# 15321_2.net
KiCad netlist of a schematic drawn in EAGLE
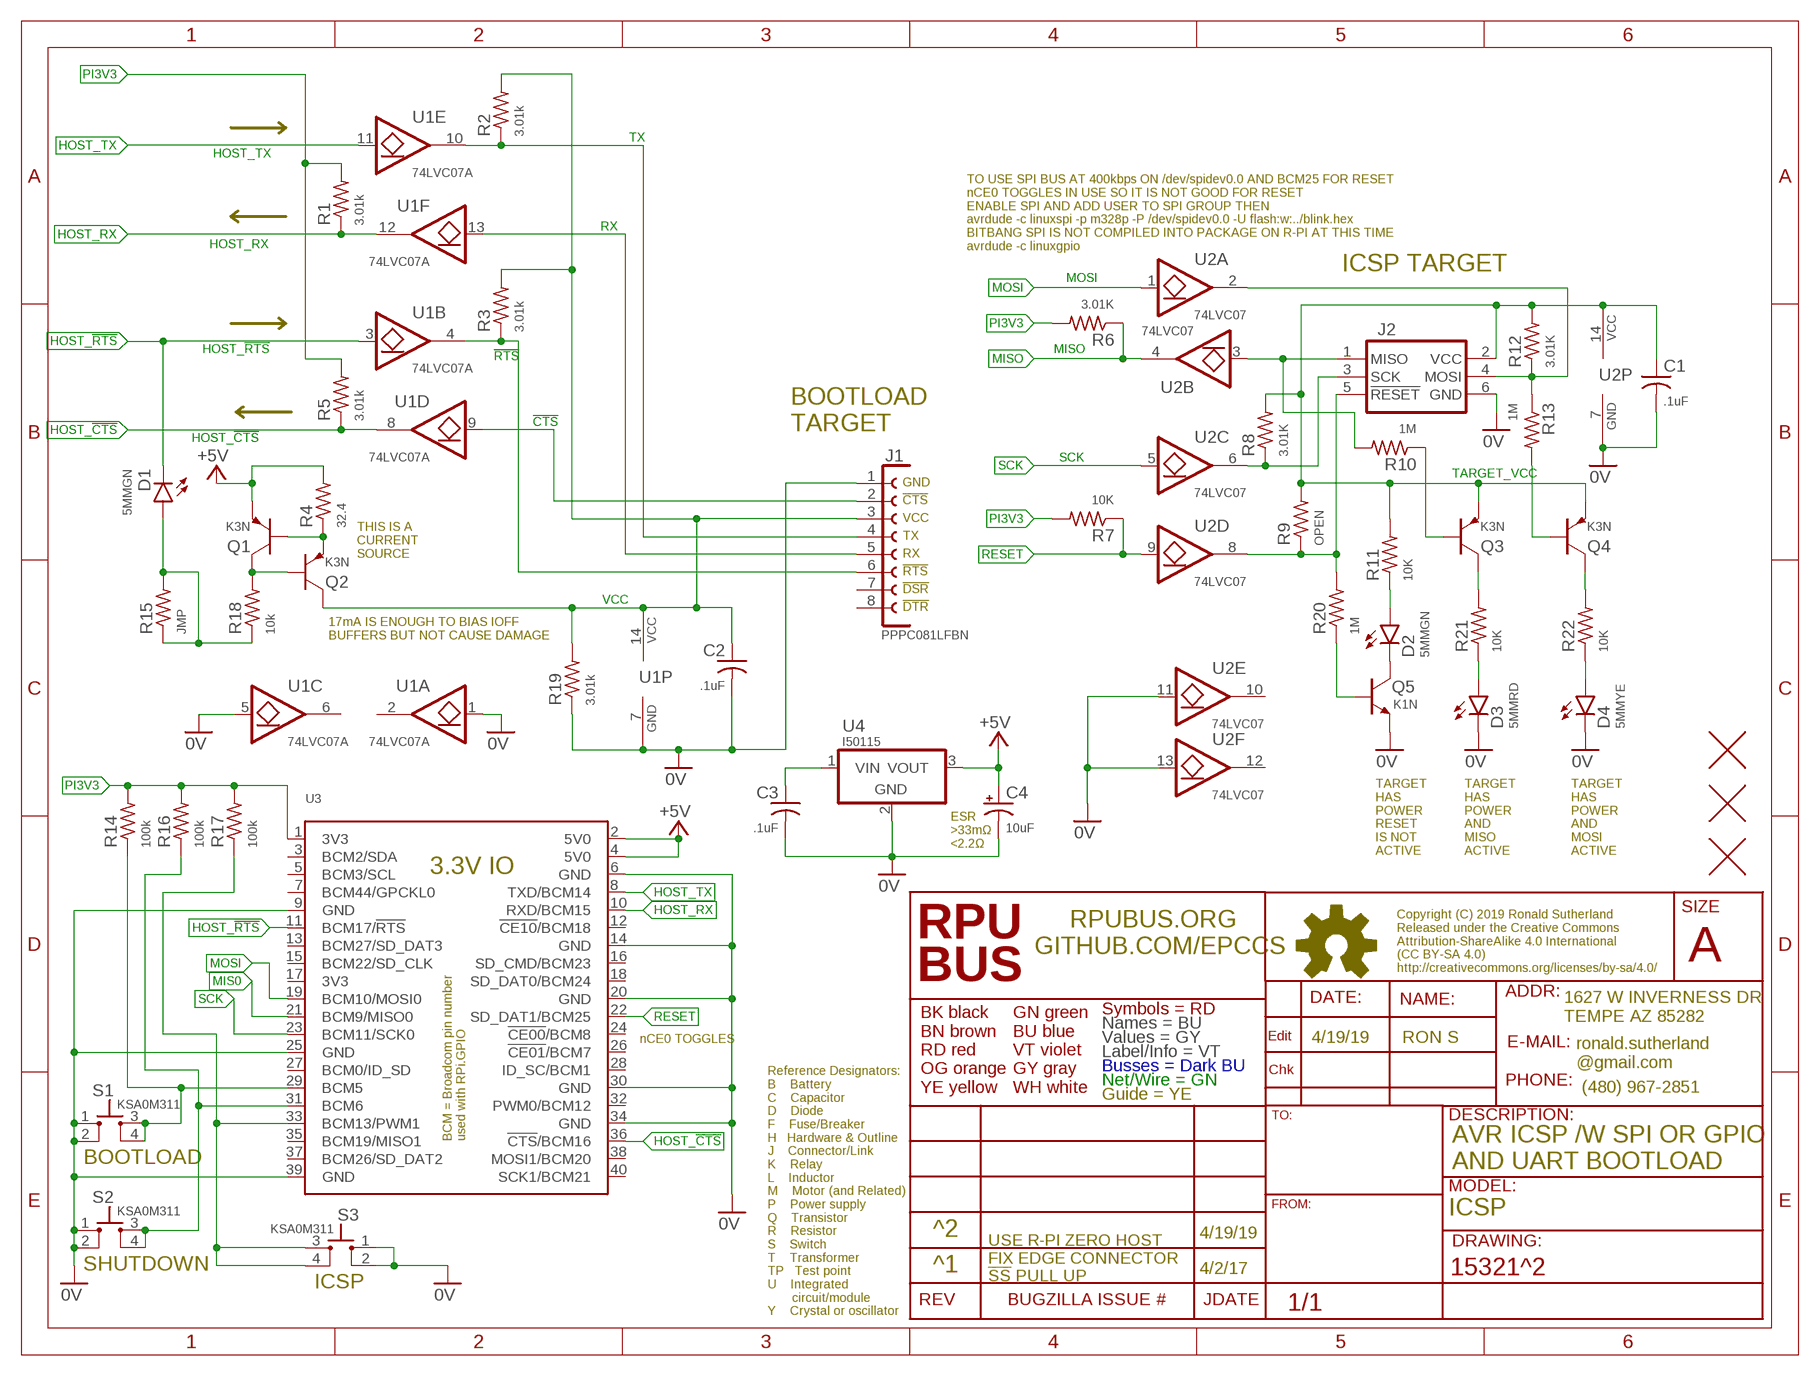
[diagram p0: schematic, sheet 1]

(export (version "E")
  (design (tool "Eeschema 10.0.6"))
  (components
    (comp (ref "C1")
      (value ".1uF")
      (footprint "eagle-import:C0603(1608)")
      (libsource (lib "eagle-import") (part "CC0603A"))
    )
    (comp (ref "C2")
      (value ".1uF")
      (footprint "eagle-import:C0603(1608)")
      (libsource (lib "eagle-import") (part "CC0603A"))
    )
    (comp (ref "C3")
      (value ".1uF")
      (footprint "eagle-import:C0603(1608)")
      (libsource (lib "eagle-import") (part "CC0603A"))
    )
    (comp (ref "C4")
      (value "10uF")
      (footprint "eagle-import:3216")
      (libsource (lib "eagle-import") (part "CT1206"))
    )
    (comp (ref "D1")
      (value "5MMGN")
      (footprint "eagle-import:LED5MM")
      (libsource (lib "eagle-import") (part "LED5MM"))
    )
    (comp (ref "D2")
      (value "5MMGN")
      (footprint "eagle-import:LED5MM")
      (libsource (lib "eagle-import") (part "LED5MM"))
    )
    (comp (ref "D3")
      (value "5MMRD")
      (footprint "eagle-import:LED5MM")
      (libsource (lib "eagle-import") (part "LED5MM"))
    )
    (comp (ref "D4")
      (value "5MMYE")
      (footprint "eagle-import:LED5MM")
      (libsource (lib "eagle-import") (part "LED5MM"))
    )
    (comp (ref "J1")
      (value "PPPC081LFBN")
      (footprint "eagle-import:F1X8")
      (libsource (lib "eagle-import") (part "F1X8"))
    )
    (comp (ref "J2")
      (value "ISP-SPIEDG")
      (footprint "eagle-import:ISP-EDG")
      (libsource (lib "eagle-import") (part "ISP-SPIEDG"))
    )
    (comp (ref "Q1")
      (value "K3N")
      (footprint "eagle-import:SOT23")
      (libsource (lib "eagle-import") (part "PNPSOT23"))
    )
    (comp (ref "Q2")
      (value "K3N")
      (footprint "eagle-import:SOT23")
      (libsource (lib "eagle-import") (part "PNPSOT23"))
    )
    (comp (ref "Q3")
      (value "K3N")
      (footprint "eagle-import:SOT23")
      (libsource (lib "eagle-import") (part "PNPSOT23"))
    )
    (comp (ref "Q4")
      (value "K3N")
      (footprint "eagle-import:SOT23")
      (libsource (lib "eagle-import") (part "PNPSOT23"))
    )
    (comp (ref "Q5")
      (value "K1N")
      (footprint "eagle-import:SOT23")
      (libsource (lib "eagle-import") (part "NPNSOT23"))
    )
    (comp (ref "R1")
      (value "3.01k")
      (footprint "eagle-import:C0805(2012)")
      (libsource (lib "eagle-import") (part "R0805"))
    )
    (comp (ref "R2")
      (value "3.01k")
      (footprint "eagle-import:C0805(2012)")
      (libsource (lib "eagle-import") (part "R0805"))
    )
    (comp (ref "R3")
      (value "3.01k")
      (footprint "eagle-import:C0805(2012)")
      (libsource (lib "eagle-import") (part "R0805"))
    )
    (comp (ref "R4")
      (value "32.4")
      (footprint "eagle-import:C0805(2012)")
      (libsource (lib "eagle-import") (part "R0805"))
    )
    (comp (ref "R5")
      (value "3.01k")
      (footprint "eagle-import:C0805(2012)")
      (libsource (lib "eagle-import") (part "R0805"))
    )
    (comp (ref "R6")
      (value "3.01K")
      (footprint "eagle-import:C0805(2012)")
      (libsource (lib "eagle-import") (part "R0805"))
    )
    (comp (ref "R7")
      (value "10K")
      (footprint "eagle-import:C0805(2012)")
      (libsource (lib "eagle-import") (part "R0805"))
    )
    (comp (ref "R8")
      (value "3.01K")
      (footprint "eagle-import:C0805(2012)")
      (libsource (lib "eagle-import") (part "R0805"))
    )
    (comp (ref "R9")
      (value "OPEN")
      (footprint "eagle-import:C0805(2012)")
      (libsource (lib "eagle-import") (part "R0805"))
    )
    (comp (ref "R10")
      (value "1M")
      (footprint "eagle-import:C0805(2012)")
      (libsource (lib "eagle-import") (part "R0805"))
    )
    (comp (ref "R11")
      (value "10K")
      (footprint "eagle-import:C0805(2012)")
      (libsource (lib "eagle-import") (part "R0805"))
    )
    (comp (ref "R12")
      (value "3.01K")
      (footprint "eagle-import:C0805(2012)")
      (libsource (lib "eagle-import") (part "R0805"))
    )
    (comp (ref "R13")
      (value "1M")
      (footprint "eagle-import:C0805(2012)")
      (libsource (lib "eagle-import") (part "R0805"))
    )
    (comp (ref "R14")
      (value "100k")
      (footprint "eagle-import:C0805(2012)")
      (libsource (lib "eagle-import") (part "R0805"))
    )
    (comp (ref "R15")
      (value "JMP")
      (footprint "eagle-import:C0805(2012)")
      (libsource (lib "eagle-import") (part "R0805"))
    )
    (comp (ref "R16")
      (value "100k")
      (footprint "eagle-import:C0805(2012)")
      (libsource (lib "eagle-import") (part "R0805"))
    )
    (comp (ref "R17")
      (value "100k")
      (footprint "eagle-import:C0805(2012)")
      (libsource (lib "eagle-import") (part "R0805"))
    )
    (comp (ref "R18")
      (value "10k")
      (footprint "eagle-import:C0805(2012)")
      (libsource (lib "eagle-import") (part "R0805"))
    )
    (comp (ref "R19")
      (value "3.01k")
      (footprint "eagle-import:C0805(2012)")
      (libsource (lib "eagle-import") (part "R0805"))
    )
    (comp (ref "R20")
      (value "1M")
      (footprint "eagle-import:C0805(2012)")
      (libsource (lib "eagle-import") (part "R0805"))
    )
    (comp (ref "R21")
      (value "10K")
      (footprint "eagle-import:C0805(2012)")
      (libsource (lib "eagle-import") (part "R0805"))
    )
    (comp (ref "R22")
      (value "10K")
      (footprint "eagle-import:C0805(2012)")
      (libsource (lib "eagle-import") (part "R0805"))
    )
    (comp (ref "S1")
      (value "KSA0M311")
      (footprint "eagle-import:0M311")
      (libsource (lib "eagle-import") (part "KSA0M311"))
    )
    (comp (ref "S2")
      (value "KSA0M311")
      (footprint "eagle-import:0M311")
      (libsource (lib "eagle-import") (part "KSA0M311"))
    )
    (comp (ref "S3")
      (value "KSA0M311")
      (footprint "eagle-import:0M311")
      (libsource (lib "eagle-import") (part "KSA0M311"))
    )
    (comp (ref "U$2")
      (value "FIDUCIAL1.27")
      (footprint "eagle-import:FIDUCIAL-1.27")
      (libsource (lib "eagle-import") (part "FIDUCIAL1.27"))
    )
    (comp (ref "U$3")
      (value "FIDUCIAL1.27")
      (footprint "eagle-import:FIDUCIAL-1.27")
      (libsource (lib "eagle-import") (part "FIDUCIAL1.27"))
    )
    (comp (ref "U$4")
      (value "FIDUCIAL1.27")
      (footprint "eagle-import:FIDUCIAL-1.27")
      (libsource (lib "eagle-import") (part "FIDUCIAL1.27"))
    )
    (comp (ref "U1")
      (value "74LVC07A")
      (footprint "eagle-import:14SOIC")
      (libsource (lib "eagle-import") (part "7407D"))
    )
    (comp (ref "U2")
      (value "74LVC07")
      (footprint "eagle-import:14SOIC")
      (libsource (lib "eagle-import") (part "7407D"))
    )
    (comp (ref "U3")
      (value "RPI-ZERO")
      (footprint "eagle-import:RASPI_ZERO_H40PIN")
      (libsource (lib "eagle-import") (part "RPI-ZERO"))
    )
    (comp (ref "U4")
      (value "I50115")
      (footprint "eagle-import:OKI-78SR-H")
      (libsource (lib "eagle-import") (part "OKI-78SR-H"))
    )
  )
  (nets
    (net (code "1") (name "+5V") (class "Default")
      (node (ref "C4") (pin "+") (pinfunction "+_+") (pintype "passive"))
      (node (ref "Q1") (pin "E") (pinfunction "E_E") (pintype "passive"))
      (node (ref "R4") (pin "2") (pinfunction "2_2") (pintype "passive"))
      (node (ref "U3") (pin "2") (pinfunction "5V0_2") (pintype "power_in"))
      (node (ref "U3") (pin "4") (pinfunction "5V0_4") (pintype "power_in"))
      (node (ref "U4") (pin "3") (pinfunction "VOUT_3") (pintype "passive"))
    )
    (net (code "2") (name "/3V3") (class "Default")
      (node (ref "U3") (pin "17") (pinfunction "3V3_17") (pintype "power_in"))
    )
    (net (code "3") (name "/HOST_~{CTS}") (class "Default")
      (node (ref "R5") (pin "1") (pinfunction "1_1") (pintype "passive"))
      (node (ref "U1") (pin "8") (pinfunction "O_8") (pintype "open_collector"))
      (node (ref "U3") (pin "36") (pinfunction "~{CTS}/BCM16_36") (pintype "bidirectional"))
    )
    (net (code "4") (name "/HOST_~{RTS}") (class "Default")
      (node (ref "D1") (pin "K") (pinfunction "K_K") (pintype "passive"))
      (node (ref "U1") (pin "3") (pinfunction "I_3") (pintype "input"))
      (node (ref "U3") (pin "11") (pinfunction "BCM17/~{RTS}_11") (pintype "bidirectional"))
    )
    (net (code "5") (name "/RX") (class "Default")
      (node (ref "J1") (pin "5") (pinfunction "5_5") (pintype "passive"))
      (node (ref "U1") (pin "13") (pinfunction "I_13") (pintype "input"))
    )
    (net (code "6") (name "/TARGET_VCC") (class "Default")
      (node (ref "C1") (pin "1") (pinfunction "1_1") (pintype "passive"))
      (node (ref "J2") (pin "2") (pinfunction "VCC_2") (pintype "bidirectional"))
      (node (ref "Q3") (pin "E") (pinfunction "E_E") (pintype "passive"))
      (node (ref "Q4") (pin "E") (pinfunction "E_E") (pintype "passive"))
      (node (ref "R11") (pin "2") (pinfunction "2_2") (pintype "passive"))
      (node (ref "R12") (pin "2") (pinfunction "2_2") (pintype "passive"))
      (node (ref "R8") (pin "2") (pinfunction "2_2") (pintype "passive"))
      (node (ref "R9") (pin "2") (pinfunction "2_2") (pintype "passive"))
      (node (ref "U2") (pin "14") (pinfunction "VCC_14") (pintype "power_in"))
    )
    (net (code "7") (name "/TX") (class "Default")
      (node (ref "J1") (pin "4") (pinfunction "4_4") (pintype "passive"))
      (node (ref "R2") (pin "1") (pinfunction "1_1") (pintype "passive"))
      (node (ref "U1") (pin "10") (pinfunction "O_10") (pintype "open_collector"))
    )
    (net (code "8") (name "/VCC") (class "Default")
      (node (ref "C2") (pin "1") (pinfunction "1_1") (pintype "passive"))
      (node (ref "J1") (pin "3") (pinfunction "3_3") (pintype "passive"))
      (node (ref "Q2") (pin "C") (pinfunction "C_C") (pintype "passive"))
      (node (ref "R19") (pin "2") (pinfunction "2_2") (pintype "passive"))
      (node (ref "R2") (pin "2") (pinfunction "2_2") (pintype "passive"))
      (node (ref "R3") (pin "2") (pinfunction "2_2") (pintype "passive"))
      (node (ref "U1") (pin "14") (pinfunction "VCC_14") (pintype "power_in"))
    )
    (net (code "9") (name "/~{CTS}") (class "Default")
      (node (ref "J1") (pin "2") (pinfunction "2_2") (pintype "passive"))
      (node (ref "U1") (pin "9") (pinfunction "I_9") (pintype "input"))
    )
    (net (code "10") (name "/~{RTS}") (class "Default")
      (node (ref "J1") (pin "6") (pinfunction "6_6") (pintype "passive"))
      (node (ref "R3") (pin "1") (pinfunction "1_1") (pintype "passive"))
      (node (ref "U1") (pin "4") (pinfunction "O_4") (pintype "open_collector"))
    )
    (net (code "11") (name "0V") (class "Default")
      (node (ref "C1") (pin "2") (pinfunction "2_2") (pintype "passive"))
      (node (ref "C2") (pin "2") (pinfunction "2_2") (pintype "passive"))
      (node (ref "C3") (pin "2") (pinfunction "2_2") (pintype "passive"))
      (node (ref "C4") (pin "-") (pinfunction "-_-") (pintype "passive"))
      (node (ref "D3") (pin "K") (pinfunction "K_K") (pintype "passive"))
      (node (ref "D4") (pin "K") (pinfunction "K_K") (pintype "passive"))
      (node (ref "J1") (pin "1") (pinfunction "1_1") (pintype "passive"))
      (node (ref "J2") (pin "6") (pinfunction "GND_6") (pintype "bidirectional"))
      (node (ref "Q5") (pin "E") (pinfunction "E_E") (pintype "passive"))
      (node (ref "R19") (pin "1") (pinfunction "1_1") (pintype "passive"))
      (node (ref "S1") (pin "1") (pinfunction "1_1") (pintype "passive"))
      (node (ref "S1") (pin "2") (pinfunction "2_2") (pintype "passive"))
      (node (ref "S2") (pin "1") (pinfunction "1_1") (pintype "passive"))
      (node (ref "S2") (pin "2") (pinfunction "2_2") (pintype "passive"))
      (node (ref "S3") (pin "1") (pinfunction "1_1") (pintype "passive"))
      (node (ref "S3") (pin "2") (pinfunction "2_2") (pintype "passive"))
      (node (ref "U1") (pin "1") (pinfunction "I_1") (pintype "input"))
      (node (ref "U1") (pin "5") (pinfunction "I_5") (pintype "input"))
      (node (ref "U1") (pin "7") (pinfunction "GND_7") (pintype "power_in"))
      (node (ref "U2") (pin "11") (pinfunction "I_11") (pintype "input"))
      (node (ref "U2") (pin "13") (pinfunction "I_13") (pintype "input"))
      (node (ref "U2") (pin "7") (pinfunction "GND_7") (pintype "power_in"))
      (node (ref "U3") (pin "14") (pinfunction "GND_14") (pintype "power_in"))
      (node (ref "U3") (pin "20") (pinfunction "GND_20") (pintype "power_in"))
      (node (ref "U3") (pin "25") (pinfunction "GND_25") (pintype "power_in"))
      (node (ref "U3") (pin "30") (pinfunction "GND_30") (pintype "power_in"))
      (node (ref "U3") (pin "34") (pinfunction "GND_34") (pintype "power_in"))
      (node (ref "U3") (pin "39") (pinfunction "GND_39") (pintype "power_in"))
      (node (ref "U3") (pin "6") (pinfunction "GND_6") (pintype "power_in"))
      (node (ref "U3") (pin "9") (pinfunction "GND_9") (pintype "power_in"))
      (node (ref "U4") (pin "2") (pinfunction "GND_2") (pintype "passive"))
    )
    (net (code "12") (name "HOST_RX") (class "Default")
      (node (ref "R1") (pin "1") (pinfunction "1_1") (pintype "passive"))
      (node (ref "U1") (pin "12") (pinfunction "O_12") (pintype "open_collector"))
      (node (ref "U3") (pin "10") (pinfunction "RXD/BCM15_10") (pintype "bidirectional"))
    )
    (net (code "13") (name "HOST_TX") (class "Default")
      (node (ref "U1") (pin "11") (pinfunction "I_11") (pintype "input"))
      (node (ref "U3") (pin "8") (pinfunction "TXD/BCM14_8") (pintype "bidirectional"))
    )
    (net (code "14") (name "MIS0") (class "Default")
      (node (ref "U3") (pin "21") (pinfunction "BCM9/MISO0_21") (pintype "bidirectional"))
    )
    (net (code "15") (name "MISO") (class "Default")
      (node (ref "R6") (pin "1") (pinfunction "1_1") (pintype "passive"))
      (node (ref "U2") (pin "4") (pinfunction "O_4") (pintype "open_collector"))
    )
    (net (code "16") (name "MOSI") (class "Default")
      (node (ref "U2") (pin "1") (pinfunction "I_1") (pintype "input"))
      (node (ref "U3") (pin "19") (pinfunction "BCM10/MOSI0_19") (pintype "bidirectional"))
    )
    (net (code "17") (name "Net-(D1-PadA)") (class "Default")
      (node (ref "D1") (pin "A") (pinfunction "A_A") (pintype "passive"))
      (node (ref "R15") (pin "1") (pinfunction "1_1") (pintype "passive"))
      (node (ref "R15") (pin "2") (pinfunction "2_2") (pintype "passive"))
      (node (ref "R18") (pin "1") (pinfunction "1_1") (pintype "passive"))
    )
    (net (code "18") (name "Net-(D2-PadA)") (class "Default")
      (node (ref "D2") (pin "A") (pinfunction "A_A") (pintype "passive"))
      (node (ref "R11") (pin "1") (pinfunction "1_1") (pintype "passive"))
    )
    (net (code "19") (name "Net-(D2-PadK)") (class "Default")
      (node (ref "D2") (pin "K") (pinfunction "K_K") (pintype "passive"))
      (node (ref "Q5") (pin "C") (pinfunction "C_C") (pintype "passive"))
    )
    (net (code "20") (name "Net-(D3-PadA)") (class "Default")
      (node (ref "D3") (pin "A") (pinfunction "A_A") (pintype "passive"))
      (node (ref "R21") (pin "1") (pinfunction "1_1") (pintype "passive"))
    )
    (net (code "21") (name "Net-(D4-PadA)") (class "Default")
      (node (ref "D4") (pin "A") (pinfunction "A_A") (pintype "passive"))
      (node (ref "R22") (pin "1") (pinfunction "1_1") (pintype "passive"))
    )
    (net (code "22") (name "Net-(J2-MISO)") (class "Default")
      (node (ref "J2") (pin "1") (pinfunction "MISO_1") (pintype "bidirectional"))
      (node (ref "R10") (pin "2") (pinfunction "2_2") (pintype "passive"))
      (node (ref "U2") (pin "3") (pinfunction "I_3") (pintype "input"))
    )
    (net (code "23") (name "Net-(J2-MOSI)") (class "Default")
      (node (ref "J2") (pin "4") (pinfunction "MOSI_4") (pintype "bidirectional"))
      (node (ref "R12") (pin "1") (pinfunction "1_1") (pintype "passive"))
      (node (ref "R13") (pin "1") (pinfunction "1_1") (pintype "passive"))
      (node (ref "U2") (pin "2") (pinfunction "O_2") (pintype "open_collector"))
    )
    (net (code "24") (name "Net-(J2-SCK)") (class "Default")
      (node (ref "J2") (pin "3") (pinfunction "SCK_3") (pintype "bidirectional"))
      (node (ref "R8") (pin "1") (pinfunction "1_1") (pintype "passive"))
      (node (ref "U2") (pin "6") (pinfunction "O_6") (pintype "open_collector"))
    )
    (net (code "25") (name "Net-(J2-~{RESET})") (class "Default")
      (node (ref "J2") (pin "5") (pinfunction "~{RESET}_5") (pintype "bidirectional"))
      (node (ref "R20") (pin "2") (pinfunction "2_2") (pintype "passive"))
      (node (ref "R9") (pin "1") (pinfunction "1_1") (pintype "passive"))
      (node (ref "U2") (pin "8") (pinfunction "O_8") (pintype "open_collector"))
    )
    (net (code "26") (name "Net-(Q1-PadB)") (class "Default")
      (node (ref "Q1") (pin "B") (pinfunction "B_B") (pintype "passive"))
      (node (ref "Q2") (pin "E") (pinfunction "E_E") (pintype "passive"))
      (node (ref "R4") (pin "1") (pinfunction "1_1") (pintype "passive"))
    )
    (net (code "27") (name "Net-(Q1-PadC)") (class "Default")
      (node (ref "Q1") (pin "C") (pinfunction "C_C") (pintype "passive"))
      (node (ref "Q2") (pin "B") (pinfunction "B_B") (pintype "passive"))
      (node (ref "R18") (pin "2") (pinfunction "2_2") (pintype "passive"))
    )
    (net (code "28") (name "Net-(Q3-PadB)") (class "Default")
      (node (ref "Q3") (pin "B") (pinfunction "B_B") (pintype "passive"))
      (node (ref "R10") (pin "1") (pinfunction "1_1") (pintype "passive"))
    )
    (net (code "29") (name "Net-(Q3-PadC)") (class "Default")
      (node (ref "Q3") (pin "C") (pinfunction "C_C") (pintype "passive"))
      (node (ref "R21") (pin "2") (pinfunction "2_2") (pintype "passive"))
    )
    (net (code "30") (name "Net-(Q4-PadB)") (class "Default")
      (node (ref "Q4") (pin "B") (pinfunction "B_B") (pintype "passive"))
      (node (ref "R13") (pin "2") (pinfunction "2_2") (pintype "passive"))
    )
    (net (code "31") (name "Net-(Q4-PadC)") (class "Default")
      (node (ref "Q4") (pin "C") (pinfunction "C_C") (pintype "passive"))
      (node (ref "R22") (pin "2") (pinfunction "2_2") (pintype "passive"))
    )
    (net (code "32") (name "Net-(Q5-PadB)") (class "Default")
      (node (ref "Q5") (pin "B") (pinfunction "B_B") (pintype "passive"))
      (node (ref "R20") (pin "1") (pinfunction "1_1") (pintype "passive"))
    )
    (net (code "33") (name "Net-(U3-BCM5)") (class "Default")
      (node (ref "R14") (pin "1") (pinfunction "1_1") (pintype "passive"))
      (node (ref "S1") (pin "3") (pinfunction "3_3") (pintype "passive"))
      (node (ref "S1") (pin "4") (pinfunction "4_4") (pintype "passive"))
      (node (ref "U3") (pin "29") (pinfunction "BCM5_29") (pintype "bidirectional"))
    )
    (net (code "34") (name "Net-(U3-BCM6)") (class "Default")
      (node (ref "R16") (pin "1") (pinfunction "1_1") (pintype "passive"))
      (node (ref "S2") (pin "3") (pinfunction "3_3") (pintype "passive"))
      (node (ref "S2") (pin "4") (pinfunction "4_4") (pintype "passive"))
      (node (ref "U3") (pin "31") (pinfunction "BCM6_31") (pintype "bidirectional"))
    )
    (net (code "35") (name "Net-(U3-BCM13{slash}PWM1)") (class "Default")
      (node (ref "R17") (pin "1") (pinfunction "1_1") (pintype "passive"))
      (node (ref "S3") (pin "3") (pinfunction "3_3") (pintype "passive"))
      (node (ref "S3") (pin "4") (pinfunction "4_4") (pintype "passive"))
      (node (ref "U3") (pin "33") (pinfunction "BCM13/PWM1_33") (pintype "bidirectional"))
    )
    (net (code "36") (name "Net-(U4-VIN)") (class "Default")
      (node (ref "C3") (pin "1") (pinfunction "1_1") (pintype "passive"))
      (node (ref "U4") (pin "1") (pinfunction "VIN_1") (pintype "passive"))
    )
    (net (code "37") (name "PI3V3") (class "Default")
      (node (ref "R1") (pin "2") (pinfunction "2_2") (pintype "passive"))
      (node (ref "R14") (pin "2") (pinfunction "2_2") (pintype "passive"))
      (node (ref "R16") (pin "2") (pinfunction "2_2") (pintype "passive"))
      (node (ref "R17") (pin "2") (pinfunction "2_2") (pintype "passive"))
      (node (ref "R5") (pin "2") (pinfunction "2_2") (pintype "passive"))
      (node (ref "R6") (pin "2") (pinfunction "2_2") (pintype "passive"))
      (node (ref "R7") (pin "2") (pinfunction "2_2") (pintype "passive"))
      (node (ref "U3") (pin "1") (pinfunction "3V3_1") (pintype "power_in"))
    )
    (net (code "38") (name "RESET") (class "Default")
      (node (ref "R7") (pin "1") (pinfunction "1_1") (pintype "passive"))
      (node (ref "U2") (pin "9") (pinfunction "I_9") (pintype "input"))
      (node (ref "U3") (pin "22") (pinfunction "SD_DAT1/BCM25_22") (pintype "bidirectional"))
    )
    (net (code "39") (name "SCK") (class "Default")
      (node (ref "U2") (pin "5") (pinfunction "I_5") (pintype "input"))
      (node (ref "U3") (pin "23") (pinfunction "BCM11/SCK0_23") (pintype "bidirectional"))
    )
    (net (code "40") (name "unconnected-(J1-Pad7)") (class "Default")
      (node (ref "J1") (pin "7") (pinfunction "7_7") (pintype "passive"))
    )
    (net (code "41") (name "unconnected-(J1-Pad8)") (class "Default")
      (node (ref "J1") (pin "8") (pinfunction "8_8") (pintype "passive"))
    )
    (net (code "42") (name "unconnected-(U1A-O-Pad2)") (class "Default")
      (node (ref "U1") (pin "2") (pinfunction "O_2") (pintype "open_collector"))
    )
    (net (code "43") (name "unconnected-(U1C-O-Pad6)") (class "Default")
      (node (ref "U1") (pin "6") (pinfunction "O_6") (pintype "open_collector"))
    )
    (net (code "44") (name "unconnected-(U2E-O-Pad10)") (class "Default")
      (node (ref "U2") (pin "10") (pinfunction "O_10") (pintype "open_collector"))
    )
    (net (code "45") (name "unconnected-(U2F-O-Pad12)") (class "Default")
      (node (ref "U2") (pin "12") (pinfunction "O_12") (pintype "open_collector"))
    )
    (net (code "46") (name "unconnected-(U3-BCM0{slash}ID_SD-Pad27)") (class "Default")
      (node (ref "U3") (pin "27") (pinfunction "BCM0/ID_SD_27") (pintype "bidirectional"))
    )
    (net (code "47") (name "unconnected-(U3-BCM2{slash}SDA-Pad3)") (class "Default")
      (node (ref "U3") (pin "3") (pinfunction "BCM2/SDA_3") (pintype "bidirectional"))
    )
    (net (code "48") (name "unconnected-(U3-BCM3{slash}SCL-Pad5)") (class "Default")
      (node (ref "U3") (pin "5") (pinfunction "BCM3/SCL_5") (pintype "bidirectional"))
    )
    (net (code "49") (name "unconnected-(U3-BCM19{slash}MISO1-Pad35)") (class "Default")
      (node (ref "U3") (pin "35") (pinfunction "BCM19/MISO1_35") (pintype "bidirectional"))
    )
    (net (code "50") (name "unconnected-(U3-BCM22{slash}SD_CLK-Pad15)") (class "Default")
      (node (ref "U3") (pin "15") (pinfunction "BCM22/SD_CLK_15") (pintype "bidirectional"))
    )
    (net (code "51") (name "unconnected-(U3-BCM26{slash}SD_DAT2-Pad37)") (class "Default")
      (node (ref "U3") (pin "37") (pinfunction "BCM26/SD_DAT2_37") (pintype "bidirectional"))
    )
    (net (code "52") (name "unconnected-(U3-BCM27{slash}SD_DAT3-Pad13)") (class "Default")
      (node (ref "U3") (pin "13") (pinfunction "BCM27/SD_DAT3_13") (pintype "bidirectional"))
    )
    (net (code "53") (name "unconnected-(U3-BCM44{slash}GPCKL0-Pad7)") (class "Default")
      (node (ref "U3") (pin "7") (pinfunction "BCM44/GPCKL0_7") (pintype "bidirectional"))
    )
    (net (code "54") (name "unconnected-(U3-ID_SC{slash}BCM1-Pad28)") (class "Default")
      (node (ref "U3") (pin "28") (pinfunction "ID_SC/BCM1_28") (pintype "bidirectional"))
    )
    (net (code "55") (name "unconnected-(U3-MOSI1{slash}BCM20-Pad38)") (class "Default")
      (node (ref "U3") (pin "38") (pinfunction "MOSI1/BCM20_38") (pintype "bidirectional"))
    )
    (net (code "56") (name "unconnected-(U3-PWM0{slash}BCM12-Pad32)") (class "Default")
      (node (ref "U3") (pin "32") (pinfunction "PWM0/BCM12_32") (pintype "bidirectional"))
    )
    (net (code "57") (name "unconnected-(U3-SCK1{slash}BCM21-Pad40)") (class "Default")
      (node (ref "U3") (pin "40") (pinfunction "SCK1/BCM21_40") (pintype "bidirectional"))
    )
    (net (code "58") (name "unconnected-(U3-SD_CMD{slash}BCM23-Pad16)") (class "Default")
      (node (ref "U3") (pin "16") (pinfunction "SD_CMD/BCM23_16") (pintype "bidirectional"))
    )
    (net (code "59") (name "unconnected-(U3-SD_DAT0{slash}BCM24-Pad18)") (class "Default")
      (node (ref "U3") (pin "18") (pinfunction "SD_DAT0/BCM24_18") (pintype "bidirectional"))
    )
    (net (code "60") (name "unconnected-(U3-~{CE00}{slash}BCM8-Pad24)") (class "Default")
      (node (ref "U3") (pin "24") (pinfunction "~{CE00}/BCM8_24") (pintype "bidirectional"))
    )
    (net (code "61") (name "unconnected-(U3-~{CE01}{slash}BCM7-Pad26)") (class "Default")
      (node (ref "U3") (pin "26") (pinfunction "~{CE01}/BCM7_26") (pintype "bidirectional"))
    )
    (net (code "62") (name "unconnected-(U3-~{CE10}{slash}BCM18-Pad12)") (class "Default")
      (node (ref "U3") (pin "12") (pinfunction "~{CE10}/BCM18_12") (pintype "bidirectional"))
    )
  )
)
